# solenoid.net
KiCad netlist of a schematic drawn in Altium Designer
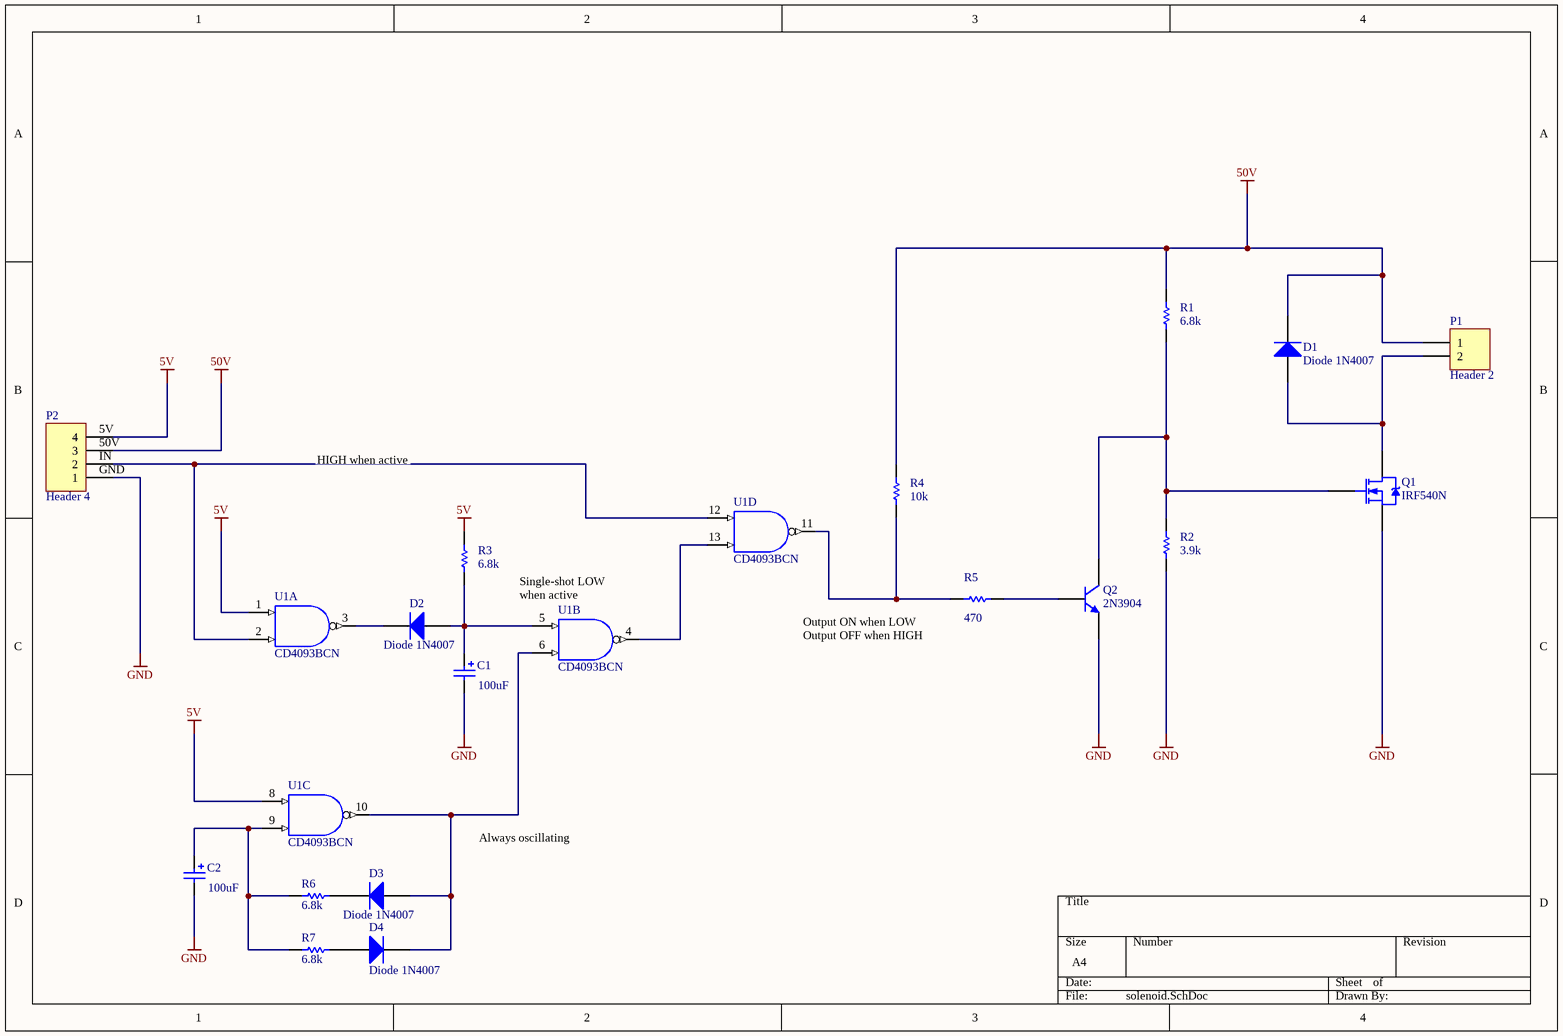
[diagram p0: solenoid.SchDoc]

(export (version "E")
  (design (tool "Eeschema 10.0.6"))
  (components
    (comp (ref "C1")
      (value "100uF")
      (footprint "POLAR0.8")
      (description "Polarized Capacitor (Axial)")
      (fields (field (name "Comment") "Cap Pol2") (field (name "PUBLISHER") "Altium Limited"))
      (libsource (lib "Miscellaneous Devices") (part "Cap Pol2"))
    )
    (comp (ref "C2")
      (value "100uF")
      (footprint "POLAR0.8")
      (description "Polarized Capacitor (Axial)")
      (fields (field (name "Comment") "Cap Pol2") (field (name "PUBLISHER") "Altium Limited"))
      (libsource (lib "Miscellaneous Devices") (part "Cap Pol2"))
    )
    (comp (ref "D1")
      (value "Diode 1N4007")
      (footprint "DO-41")
      (description "1 Amp General Purpose Rectifier")
      (fields (field (name "PUBLISHER") "Altium Limited"))
      (libsource (lib "Miscellaneous Devices") (part "Diode 1N4007"))
    )
    (comp (ref "D2")
      (value "Diode 1N4007")
      (footprint "DO-41")
      (description "1 Amp General Purpose Rectifier")
      (fields (field (name "PUBLISHER") "Altium Limited"))
      (libsource (lib "Miscellaneous Devices") (part "Diode 1N4007"))
    )
    (comp (ref "D3")
      (value "Diode 1N4007")
      (footprint "DO-41")
      (description "1 Amp General Purpose Rectifier")
      (fields (field (name "PUBLISHER") "Altium Limited"))
      (libsource (lib "Miscellaneous Devices") (part "Diode 1N4007"))
    )
    (comp (ref "D4")
      (value "Diode 1N4007")
      (footprint "DO-41")
      (description "1 Amp General Purpose Rectifier")
      (fields (field (name "PUBLISHER") "Altium Limited"))
      (libsource (lib "Miscellaneous Devices") (part "Diode 1N4007"))
    )
    (comp (ref "P1")
      (value "Header 2")
      (footprint "HDR1X2")
      (description "Header, 2-Pin")
      (fields (field (name "PUBLISHER") "Altium Limited"))
      (libsource (lib "Miscellaneous Connectors") (part "Header 2"))
    )
    (comp (ref "P2")
      (value "Header 4")
      (footprint "HDR1X4")
      (description "Header, 4-Pin")
      (fields (field (name "PUBLISHER") "Altium Limited"))
      (libsource (lib "Miscellaneous Connectors") (part "Header 4"))
    )
    (comp (ref "Q1")
      (value "IRF540N")
      (footprint "TO-220AB")
      (description "HEXFET Power MOSFET")
      (fields (field (name "PUBLISHER") "Altium Limited"))
      (libsource (lib "IR Discrete MOSFET - Power") (part "IRF540N"))
    )
    (comp (ref "Q2")
      (value "2N3904")
      (footprint "TO-92A")
      (description "NPN General Purpose Amplifier")
      (fields (field (name "PUBLISHER") "Altium Limited"))
      (libsource (lib "Miscellaneous Devices") (part "2N3904"))
    )
    (comp (ref "R1")
      (value "6.8k")
      (footprint "AXIAL-0.3")
      (description "Resistor")
      (fields (field (name "Comment") "Res1") (field (name "PUBLISHER") "Altium Limited"))
      (libsource (lib "Miscellaneous Devices") (part "Res1"))
    )
    (comp (ref "R2")
      (value "3.9k")
      (footprint "AXIAL-0.3")
      (description "Resistor")
      (fields (field (name "Comment") "Res1") (field (name "PUBLISHER") "Altium Limited"))
      (libsource (lib "Miscellaneous Devices") (part "Res1"))
    )
    (comp (ref "R3")
      (value "6.8k")
      (footprint "AXIAL-0.3")
      (description "Resistor")
      (fields (field (name "Comment") "Res1") (field (name "PUBLISHER") "Altium Limited"))
      (libsource (lib "Miscellaneous Devices") (part "Res1"))
    )
    (comp (ref "R4")
      (value "10k")
      (footprint "AXIAL-0.3")
      (description "Resistor")
      (fields (field (name "Comment") "Res1") (field (name "PUBLISHER") "Altium Limited"))
      (libsource (lib "Miscellaneous Devices") (part "Res1"))
    )
    (comp (ref "R5")
      (value "470")
      (footprint "AXIAL-0.3")
      (description "Resistor")
      (fields (field (name "Comment") "Res1") (field (name "PUBLISHER") "Altium Limited"))
      (libsource (lib "Miscellaneous Devices") (part "Res1"))
    )
    (comp (ref "R6")
      (value "6.8k")
      (footprint "AXIAL-0.3")
      (description "Resistor")
      (fields (field (name "Comment") "Res1") (field (name "PUBLISHER") "Altium Limited"))
      (libsource (lib "Miscellaneous Devices") (part "Res1"))
    )
    (comp (ref "R7")
      (value "6.8k")
      (footprint "AXIAL-0.3")
      (description "Resistor")
      (fields (field (name "Comment") "Res1") (field (name "PUBLISHER") "Altium Limited"))
      (libsource (lib "Miscellaneous Devices") (part "Res1"))
    )
    (comp (ref "U1")
      (value "CD4093BCN")
      (footprint "N14A")
      (description "Quad 2-Input Schmitt-Trigger NAND Gate, 14-Pin PDIP")
      (fields (field (name "PUBLISHER") "Altium Limited"))
      (libsource (lib "FSC Logic Gate") (part "CD4093BCN"))
    )
  )
  (nets
    (net (code "1") (name "5V") (class "Default")
      (node (ref "P2") (pin "5V") (pinfunction "4_5V") (pintype "passive"))
      (node (ref "R3") (pin "2") (pinfunction "2_2") (pintype "passive"))
      (node (ref "U1") (pin "1") (pinfunction "A_1") (pintype "input"))
      (node (ref "U1") (pin "8") (pinfunction "E_8") (pintype "input"))
    )
    (net (code "2") (name "50V") (class "Default")
      (node (ref "D1") (pin "2") (pinfunction "K_2") (pintype "passive"))
      (node (ref "P1") (pin "1") (pinfunction "1_1") (pintype "passive"))
      (node (ref "P2") (pin "50V") (pinfunction "3_50V") (pintype "passive"))
      (node (ref "R1") (pin "2") (pinfunction "2_2") (pintype "passive"))
      (node (ref "R4") (pin "2") (pinfunction "2_2") (pintype "passive"))
    )
    (net (code "3") (name "GND") (class "Default")
      (node (ref "C1") (pin "2") (pinfunction "2_2") (pintype "passive"))
      (node (ref "C2") (pin "2") (pinfunction "2_2") (pintype "passive"))
      (node (ref "P2") (pin "GND") (pinfunction "1_GND") (pintype "passive"))
      (node (ref "Q1") (pin "3") (pinfunction "S_3") (pintype "passive"))
      (node (ref "Q2") (pin "1") (pinfunction "E_1") (pintype "passive"))
      (node (ref "R2") (pin "1") (pinfunction "1_1") (pintype "passive"))
      (node (ref "U1") (pin "7") (pinfunction "GND_7") (pintype "power_in"))
    )
    (net (code "4") (name "Net-(D1-A)") (class "Default")
      (node (ref "D1") (pin "1") (pinfunction "A_1") (pintype "passive"))
      (node (ref "P1") (pin "2") (pinfunction "2_2") (pintype "passive"))
      (node (ref "Q1") (pin "2") (pinfunction "D_2") (pintype "passive"))
    )
    (net (code "5") (name "Net-(D2-A)") (class "Default")
      (node (ref "C1") (pin "1") (pinfunction "1_1") (pintype "passive"))
      (node (ref "D2") (pin "1") (pinfunction "A_1") (pintype "passive"))
      (node (ref "R3") (pin "1") (pinfunction "1_1") (pintype "passive"))
      (node (ref "U1") (pin "5") (pinfunction "C_5") (pintype "input"))
    )
    (net (code "6") (name "Net-(D2-K)") (class "Default")
      (node (ref "D2") (pin "2") (pinfunction "K_2") (pintype "passive"))
      (node (ref "U1") (pin "3") (pinfunction "J_3") (pintype "output"))
    )
    (net (code "7") (name "Net-(D3-A)") (class "Default")
      (node (ref "D3") (pin "1") (pinfunction "A_1") (pintype "passive"))
      (node (ref "D4") (pin "2") (pinfunction "K_2") (pintype "passive"))
      (node (ref "U1") (pin "10") (pinfunction "L_10") (pintype "output"))
      (node (ref "U1") (pin "6") (pinfunction "D_6") (pintype "input"))
    )
    (net (code "8") (name "Net-(D3-K)") (class "Default")
      (node (ref "D3") (pin "2") (pinfunction "K_2") (pintype "passive"))
      (node (ref "R6") (pin "1") (pinfunction "1_1") (pintype "passive"))
    )
    (net (code "9") (name "Net-(D4-A)") (class "Default")
      (node (ref "D4") (pin "1") (pinfunction "A_1") (pintype "passive"))
      (node (ref "R7") (pin "1") (pinfunction "1_1") (pintype "passive"))
    )
    (net (code "10") (name "Net-(P2-2)") (class "Default")
      (node (ref "P2") (pin "IN") (pinfunction "2_IN") (pintype "passive"))
      (node (ref "U1") (pin "12") (pinfunction "G_12") (pintype "input"))
      (node (ref "U1") (pin "2") (pinfunction "B_2") (pintype "input"))
    )
    (net (code "11") (name "Net-(Q1-G)") (class "Default")
      (node (ref "Q1") (pin "1") (pinfunction "G_1") (pintype "passive"))
      (node (ref "Q2") (pin "3") (pinfunction "C_3") (pintype "passive"))
      (node (ref "R1") (pin "1") (pinfunction "1_1") (pintype "passive"))
      (node (ref "R2") (pin "2") (pinfunction "2_2") (pintype "passive"))
    )
    (net (code "12") (name "Net-(Q2-B)") (class "Default")
      (node (ref "Q2") (pin "2") (pinfunction "B_2") (pintype "passive"))
      (node (ref "R5") (pin "1") (pinfunction "1_1") (pintype "passive"))
    )
    (net (code "13") (name "Net-(U1B-K)") (class "Default")
      (node (ref "U1") (pin "13") (pinfunction "H_13") (pintype "input"))
      (node (ref "U1") (pin "4") (pinfunction "K_4") (pintype "output"))
    )
    (net (code "14") (name "Net-(U1C-F)") (class "Default")
      (node (ref "C2") (pin "1") (pinfunction "1_1") (pintype "passive"))
      (node (ref "R6") (pin "2") (pinfunction "2_2") (pintype "passive"))
      (node (ref "R7") (pin "2") (pinfunction "2_2") (pintype "passive"))
      (node (ref "U1") (pin "9") (pinfunction "F_9") (pintype "input"))
    )
    (net (code "15") (name "Net-(U1D-M)") (class "Default")
      (node (ref "R4") (pin "1") (pinfunction "1_1") (pintype "passive"))
      (node (ref "R5") (pin "2") (pinfunction "2_2") (pintype "passive"))
      (node (ref "U1") (pin "11") (pinfunction "M_11") (pintype "output"))
    )
    (net (code "16") (name "VCC") (class "Default")
      (node (ref "U1") (pin "14") (pinfunction "VCC_14") (pintype "power_in"))
    )
  )
)
